# DECAWAVE.net
KiCad netlist of a schematic drawn in Altium Designer
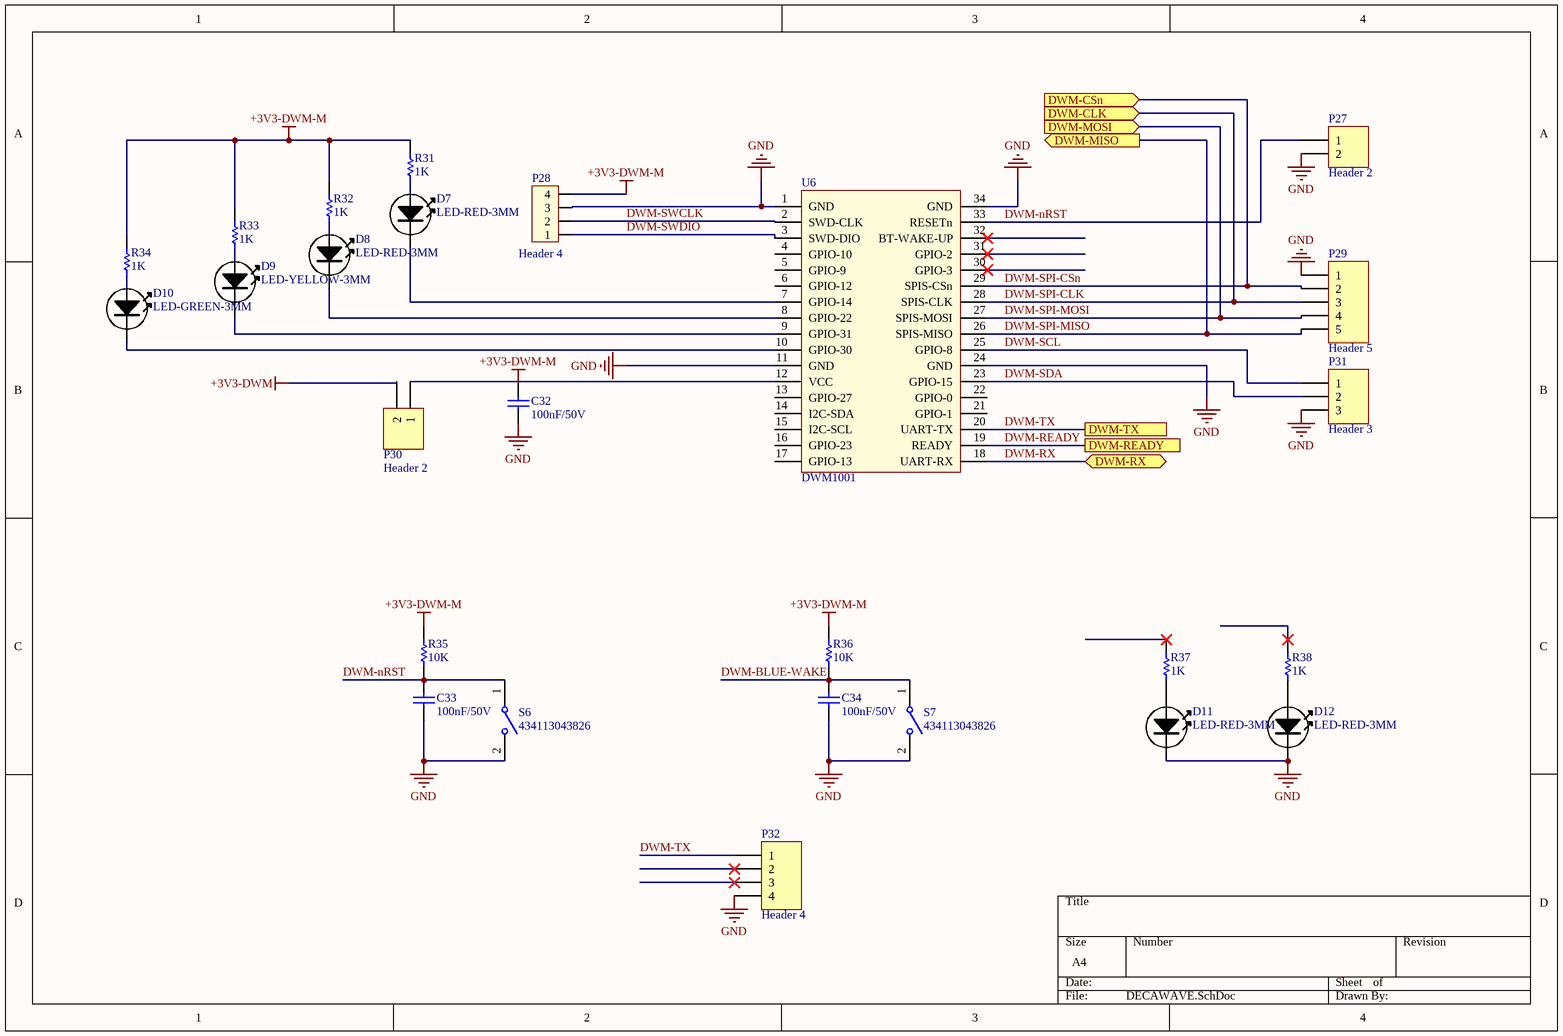
[diagram p0: DECAWAVE.SchDoc]

(export (version "E")
  (design (tool "Eeschema 10.0.6"))
  (components
    (comp (ref "C32")
      (value "100nF/50V")
      (footprint "CAP-SM-0805")
      (description "CAP CER 0.1UF 50V Y5V 0805")
      (fields
        (field (name "MANUFACTURER") "Samsung Electro-Mechanics")
        (field (name "MANUFACTURER PART NUMBER") "CL21F104ZBCNNNC")
      )
      (libsource (lib "Capacitor") (part "Cap-100nF-50V-0805"))
    )
    (comp (ref "C33")
      (value "100nF/50V")
      (footprint "CAP-SM-0805")
      (description "CAP CER 0.1UF 50V Y5V 0805")
      (fields
        (field (name "MANUFACTURER") "Samsung Electro-Mechanics")
        (field (name "MANUFACTURER PART NUMBER") "CL21F104ZBCNNNC")
      )
      (libsource (lib "Capacitor") (part "Cap-100nF-50V-0805"))
    )
    (comp (ref "C34")
      (value "100nF/50V")
      (footprint "CAP-SM-0805")
      (description "CAP CER 0.1UF 50V Y5V 0805")
      (fields
        (field (name "MANUFACTURER") "Samsung Electro-Mechanics")
        (field (name "MANUFACTURER PART NUMBER") "CL21F104ZBCNNNC")
      )
      (libsource (lib "Capacitor") (part "Cap-100nF-50V-0805"))
    )
    (comp (ref "D7")
      (value "LED-RED-3MM")
      (footprint "LED-3MM-RED")
      (libsource (lib "vh_altium_library") (part "LED-RED-3MM"))
    )
    (comp (ref "D8")
      (value "LED-RED-3MM")
      (footprint "LED-3MM-RED")
      (libsource (lib "vh_altium_library") (part "LED-RED-3MM"))
    )
    (comp (ref "D9")
      (value "LED-YELLOW-3MM")
      (footprint "LED-3MM-YELLOW")
      (libsource (lib "vh_altium_library") (part "LED-YELLOW-3MM"))
    )
    (comp (ref "D10")
      (value "LED-GREEN-3MM")
      (footprint "LED-3MM-GREEN")
      (libsource (lib "vh_altium_library") (part "LED-GREEN-3MM"))
    )
    (comp (ref "D11")
      (value "LED-RED-3MM")
      (footprint "LED-3MM-RED")
      (libsource (lib "vh_altium_library") (part "LED-RED-3MM"))
    )
    (comp (ref "D12")
      (value "LED-RED-3MM")
      (footprint "LED-3MM-RED")
      (libsource (lib "vh_altium_library") (part "LED-RED-3MM"))
    )
    (comp (ref "P27")
      (value "Header 2")
      (footprint "HDR1X2")
      (description "Header, 2-Pin")
      (fields (field (name "PUBLISHER") "Altium Limited"))
      (libsource (lib "") (part "Header 2_1"))
    )
    (comp (ref "P28")
      (value "Header 4")
      (footprint "HED4")
      (description "Header 4 (Green)")
      (libsource (lib "Library1") (part "Hed4"))
    )
    (comp (ref "P29")
      (value "Header 5")
      (footprint "HDR1X5")
      (description "Header, 5-Pin")
      (fields (field (name "PUBLISHER") "Altium Limited"))
      (libsource (lib "Library2") (part "Header 5"))
    )
    (comp (ref "P30")
      (value "Header 2")
      (footprint "HDR1X2")
      (description "Header, 2-Pin")
      (fields (field (name "PUBLISHER") "Altium Limited"))
      (libsource (lib "Library2") (part "Header 2"))
    )
    (comp (ref "P31")
      (value "Header 3")
      (footprint "HDR1X3")
      (description "Header, 3-Pin")
      (fields (field (name "PUBLISHER") "Altium Limited"))
      (libsource (lib "Library2") (part "Header 3"))
    )
    (comp (ref "P32")
      (value "Header 4")
      (footprint "HDR1X4")
      (description "Header, 4-Pin")
      (fields (field (name "PUBLISHER") "Altium Limited"))
      (libsource (lib "Library2") (part "Header 4"))
    )
    (comp (ref "R31")
      (value "1K")
      (footprint "Resistor:RES-SM-0805")
      (description "RES 1K OHM 1% 1/4W 0805")
      (fields
        (field (name "MANUFACTURER") "Stackpole Electronics Inc")
        (field (name "MANUFACTURER PART NUMBER") "RNCP0805FTD1K00")
      )
      (libsource (lib "Resistor") (part "Res-1K-0805"))
    )
    (comp (ref "R32")
      (value "1K")
      (footprint "Resistor:RES-SM-0805")
      (description "RES 1K OHM 1% 1/4W 0805")
      (fields
        (field (name "MANUFACTURER") "Stackpole Electronics Inc")
        (field (name "MANUFACTURER PART NUMBER") "RNCP0805FTD1K00")
      )
      (libsource (lib "Resistor") (part "Res-1K-0805"))
    )
    (comp (ref "R33")
      (value "1K")
      (footprint "Resistor:RES-SM-0805")
      (description "RES 1K OHM 1% 1/4W 0805")
      (fields
        (field (name "MANUFACTURER") "Stackpole Electronics Inc")
        (field (name "MANUFACTURER PART NUMBER") "RNCP0805FTD1K00")
      )
      (libsource (lib "Resistor") (part "Res-1K-0805"))
    )
    (comp (ref "R34")
      (value "1K")
      (footprint "Resistor:RES-SM-0805")
      (description "RES 1K OHM 1% 1/4W 0805")
      (fields
        (field (name "MANUFACTURER") "Stackpole Electronics Inc")
        (field (name "MANUFACTURER PART NUMBER") "RNCP0805FTD1K00")
      )
      (libsource (lib "Resistor") (part "Res-1K-0805"))
    )
    (comp (ref "R35")
      (value "10K")
      (footprint "Resistor:RES-SM-0805")
      (description "RES 10K OHM 1% 1/4W 0805")
      (fields
        (field (name "MANUFACTURER") "Stackpole Electronics Inc")
        (field (name "MANUFACTURER PART NUMBER") "RNCP0805FTD10K0")
      )
      (libsource (lib "Resistor") (part "Res-10k-0805"))
    )
    (comp (ref "R36")
      (value "10K")
      (footprint "Resistor:RES-SM-0805")
      (description "RES 10K OHM 1% 1/4W 0805")
      (fields
        (field (name "MANUFACTURER") "Stackpole Electronics Inc")
        (field (name "MANUFACTURER PART NUMBER") "RNCP0805FTD10K0")
      )
      (libsource (lib "Resistor") (part "Res-10k-0805"))
    )
    (comp (ref "R37")
      (value "1K")
      (footprint "Resistor:RES-SM-0805")
      (description "RES 1K OHM 1% 1/4W 0805")
      (fields
        (field (name "MANUFACTURER") "Stackpole Electronics Inc")
        (field (name "MANUFACTURER PART NUMBER") "RNCP0805FTD1K00")
      )
      (libsource (lib "Resistor") (part "Res-1K-0805"))
    )
    (comp (ref "R38")
      (value "1K")
      (footprint "Resistor:RES-SM-0805")
      (description "RES 1K OHM 1% 1/4W 0805")
      (fields
        (field (name "MANUFACTURER") "Stackpole Electronics Inc")
        (field (name "MANUFACTURER PART NUMBER") "RNCP0805FTD1K00")
      )
      (libsource (lib "Resistor") (part "Res-1K-0805"))
    )
    (comp (ref "S6")
      (value "434113043826")
      (footprint "434113043826")
      (description "WS-TASV J-Bend SMT Tact Switch 6x3.5mm, height 4.3mm, 260gf")
      (fields (field (name "PUBLISHER") "Wurth Elektronik"))
      (libsource (lib "434113043826_Altium_WS-TASV_rev20a") (part "434113043826"))
    )
    (comp (ref "S7")
      (value "434113043826")
      (footprint "434113043826")
      (description "WS-TASV J-Bend SMT Tact Switch 6x3.5mm, height 4.3mm, 260gf")
      (fields (field (name "PUBLISHER") "Wurth Elektronik"))
      (libsource (lib "434113043826_Altium_WS-TASV_rev20a") (part "434113043826"))
    )
    (comp (ref "U6") (value "DWM1001") (libsource (lib "MyLibrary1") (part "DWM1001")))
  )
  (nets
    (net (code "1") (name "+3V3-DWM") (class "Default")
      (node (ref "P30") (pin "2") (pinfunction "2_2") (pintype "passive"))
    )
    (net (code "2") (name "+3V3-DWM-M") (class "Default")
      (node (ref "C32") (pin "2") (pinfunction "2_2") (pintype "passive"))
      (node (ref "P28") (pin "4") (pinfunction "4_4") (pintype "passive"))
      (node (ref "R31") (pin "2") (pinfunction "2_2") (pintype "passive"))
      (node (ref "R32") (pin "2") (pinfunction "2_2") (pintype "passive"))
      (node (ref "R33") (pin "2") (pinfunction "2_2") (pintype "passive"))
      (node (ref "R34") (pin "2") (pinfunction "2_2") (pintype "passive"))
      (node (ref "R35") (pin "2") (pinfunction "2_2") (pintype "passive"))
      (node (ref "R36") (pin "2") (pinfunction "2_2") (pintype "passive"))
    )
    (net (code "3") (name "/DWM-BLUE-WAKE") (class "Default")
      (node (ref "C34") (pin "2") (pinfunction "2_2") (pintype "passive"))
      (node (ref "R36") (pin "1") (pinfunction "1_1") (pintype "passive"))
      (node (ref "S7") (pin "1") (pinfunction "1_1") (pintype "passive"))
    )
    (net (code "4") (name "/DWM-READY") (class "Default")
      (node (ref "U6") (pin "19") (pinfunction "READY_19") (pintype "passive"))
    )
    (net (code "5") (name "/DWM-RX") (class "Default")
      (node (ref "U6") (pin "18") (pinfunction "UART-RX_18") (pintype "passive"))
    )
    (net (code "6") (name "/DWM-SCL") (class "Default")
      (node (ref "P31") (pin "1") (pinfunction "1_1") (pintype "passive"))
      (node (ref "U6") (pin "25") (pinfunction "GPIO-8_25") (pintype "passive"))
    )
    (net (code "7") (name "/DWM-SDA") (class "Default")
      (node (ref "P31") (pin "2") (pinfunction "2_2") (pintype "passive"))
      (node (ref "U6") (pin "23") (pinfunction "GPIO-15_23") (pintype "passive"))
    )
    (net (code "8") (name "/DWM-SPI-CLK") (class "Default")
      (node (ref "P29") (pin "3") (pinfunction "3_3") (pintype "passive"))
      (node (ref "U6") (pin "28") (pinfunction "SPIS-CLK_28") (pintype "passive"))
    )
    (net (code "9") (name "/DWM-SPI-CSn") (class "Default")
      (node (ref "P29") (pin "2") (pinfunction "2_2") (pintype "passive"))
      (node (ref "U6") (pin "29") (pinfunction "SPIS-CSn_29") (pintype "passive"))
    )
    (net (code "10") (name "/DWM-SPI-MISO") (class "Default")
      (node (ref "P29") (pin "5") (pinfunction "5_5") (pintype "passive"))
      (node (ref "U6") (pin "26") (pinfunction "SPIS-MISO_26") (pintype "passive"))
    )
    (net (code "11") (name "/DWM-SPI-MOSI") (class "Default")
      (node (ref "P29") (pin "4") (pinfunction "4_4") (pintype "passive"))
      (node (ref "U6") (pin "27") (pinfunction "SPIS-MOSI_27") (pintype "passive"))
    )
    (net (code "12") (name "/DWM-SWCLK") (class "Default")
      (node (ref "P28") (pin "2") (pinfunction "2_2") (pintype "passive"))
      (node (ref "U6") (pin "2") (pinfunction "SWD-CLK_2") (pintype "passive"))
    )
    (net (code "13") (name "/DWM-SWDIO") (class "Default")
      (node (ref "P28") (pin "1") (pinfunction "1_1") (pintype "passive"))
      (node (ref "U6") (pin "3") (pinfunction "SWD-DIO_3") (pintype "passive"))
    )
    (net (code "14") (name "/DWM-TX") (class "Default")
      (node (ref "P32") (pin "1") (pinfunction "1_1") (pintype "passive"))
      (node (ref "U6") (pin "20") (pinfunction "UART-TX_20") (pintype "passive"))
    )
    (net (code "15") (name "/DWM-nRST") (class "Default")
      (node (ref "C33") (pin "2") (pinfunction "2_2") (pintype "passive"))
      (node (ref "P27") (pin "1") (pinfunction "1_1") (pintype "passive"))
      (node (ref "R35") (pin "1") (pinfunction "1_1") (pintype "passive"))
      (node (ref "S6") (pin "1") (pinfunction "1_1") (pintype "passive"))
      (node (ref "U6") (pin "33") (pinfunction "RESETn_33") (pintype "passive"))
    )
    (net (code "16") (name "GND") (class "Default")
      (node (ref "C32") (pin "1") (pinfunction "1_1") (pintype "passive"))
      (node (ref "C33") (pin "1") (pinfunction "1_1") (pintype "passive"))
      (node (ref "C34") (pin "1") (pinfunction "1_1") (pintype "passive"))
      (node (ref "D11") (pin "K") (pintype "passive"))
      (node (ref "D12") (pin "K") (pintype "passive"))
      (node (ref "P27") (pin "2") (pinfunction "2_2") (pintype "passive"))
      (node (ref "P28") (pin "3") (pinfunction "3_3") (pintype "passive"))
      (node (ref "P29") (pin "1") (pinfunction "1_1") (pintype "passive"))
      (node (ref "P31") (pin "3") (pinfunction "3_3") (pintype "passive"))
      (node (ref "P32") (pin "4") (pinfunction "4_4") (pintype "passive"))
      (node (ref "S6") (pin "2") (pinfunction "2_2") (pintype "passive"))
      (node (ref "S7") (pin "2") (pinfunction "2_2") (pintype "passive"))
      (node (ref "U6") (pin "1") (pinfunction "GND_1") (pintype "passive"))
      (node (ref "U6") (pin "11") (pinfunction "GND_11") (pintype "passive"))
      (node (ref "U6") (pin "24") (pinfunction "GND_24") (pintype "passive"))
      (node (ref "U6") (pin "34") (pinfunction "GND_34") (pintype "passive"))
    )
    (net (code "17") (name "Net-(D7-PadA)") (class "Default")
      (node (ref "D7") (pin "A") (pintype "passive"))
      (node (ref "R31") (pin "1") (pinfunction "1_1") (pintype "passive"))
    )
    (net (code "18") (name "Net-(D8-PadA)") (class "Default")
      (node (ref "D8") (pin "A") (pintype "passive"))
      (node (ref "R32") (pin "1") (pinfunction "1_1") (pintype "passive"))
    )
    (net (code "19") (name "Net-(D9-PadA)") (class "Default")
      (node (ref "D9") (pin "A") (pintype "passive"))
      (node (ref "R33") (pin "1") (pinfunction "1_1") (pintype "passive"))
    )
    (net (code "20") (name "Net-(D10-PadA)") (class "Default")
      (node (ref "D10") (pin "A") (pintype "passive"))
      (node (ref "R34") (pin "1") (pinfunction "1_1") (pintype "passive"))
    )
    (net (code "21") (name "Net-(D11-PadA)") (class "Default")
      (node (ref "D11") (pin "A") (pintype "passive"))
      (node (ref "R37") (pin "1") (pinfunction "1_1") (pintype "passive"))
    )
    (net (code "22") (name "Net-(D12-PadA)") (class "Default")
      (node (ref "D12") (pin "A") (pintype "passive"))
      (node (ref "R38") (pin "1") (pinfunction "1_1") (pintype "passive"))
    )
    (net (code "23") (name "Net-(U6-GPIO-14)") (class "Default")
      (node (ref "D7") (pin "K") (pintype "passive"))
      (node (ref "U6") (pin "7") (pinfunction "GPIO-14_7") (pintype "passive"))
    )
    (net (code "24") (name "Net-(U6-GPIO-22)") (class "Default")
      (node (ref "D8") (pin "K") (pintype "passive"))
      (node (ref "U6") (pin "8") (pinfunction "GPIO-22_8") (pintype "passive"))
    )
    (net (code "25") (name "Net-(U6-GPIO-30)") (class "Default")
      (node (ref "D10") (pin "K") (pintype "passive"))
      (node (ref "U6") (pin "10") (pinfunction "GPIO-30_10") (pintype "passive"))
    )
    (net (code "26") (name "Net-(U6-GPIO-31)") (class "Default")
      (node (ref "D9") (pin "K") (pintype "passive"))
      (node (ref "U6") (pin "9") (pinfunction "GPIO-31_9") (pintype "passive"))
    )
    (net (code "27") (name "Net-(U6-VCC)") (class "Default")
      (node (ref "P30") (pin "1") (pinfunction "1_1") (pintype "passive"))
      (node (ref "U6") (pin "12") (pinfunction "VCC_12") (pintype "passive"))
    )
    (net (code "28") (name "unconnected-(P32-Pad2)") (class "Default")
      (node (ref "P32") (pin "2") (pinfunction "2_2") (pintype "passive+no_connect"))
    )
    (net (code "29") (name "unconnected-(P32-Pad3)") (class "Default")
      (node (ref "P32") (pin "3") (pinfunction "3_3") (pintype "passive+no_connect"))
    )
    (net (code "30") (name "unconnected-(R37-Pad2)") (class "Default")
      (node (ref "R37") (pin "2") (pinfunction "2_2") (pintype "passive+no_connect"))
    )
    (net (code "31") (name "unconnected-(R38-Pad2)") (class "Default")
      (node (ref "R38") (pin "2") (pinfunction "2_2") (pintype "passive+no_connect"))
    )
    (net (code "32") (name "unconnected-(U6-BT-WAKE-UP-Pad32)") (class "Default")
      (node (ref "U6") (pin "32") (pinfunction "BT-WAKE-UP_32") (pintype "passive+no_connect"))
    )
    (net (code "33") (name "unconnected-(U6-GPIO-0-Pad22)") (class "Default")
      (node (ref "U6") (pin "22") (pinfunction "GPIO-0_22") (pintype "passive"))
    )
    (net (code "34") (name "unconnected-(U6-GPIO-1-Pad21)") (class "Default")
      (node (ref "U6") (pin "21") (pinfunction "GPIO-1_21") (pintype "passive"))
    )
    (net (code "35") (name "unconnected-(U6-GPIO-2-Pad31)") (class "Default")
      (node (ref "U6") (pin "31") (pinfunction "GPIO-2_31") (pintype "passive+no_connect"))
    )
    (net (code "36") (name "unconnected-(U6-GPIO-3-Pad30)") (class "Default")
      (node (ref "U6") (pin "30") (pinfunction "GPIO-3_30") (pintype "passive+no_connect"))
    )
    (net (code "37") (name "unconnected-(U6-GPIO-9-Pad5)") (class "Default")
      (node (ref "U6") (pin "5") (pinfunction "GPIO-9_5") (pintype "passive"))
    )
    (net (code "38") (name "unconnected-(U6-GPIO-10-Pad4)") (class "Default")
      (node (ref "U6") (pin "4") (pinfunction "GPIO-10_4") (pintype "passive"))
    )
    (net (code "39") (name "unconnected-(U6-GPIO-12-Pad6)") (class "Default")
      (node (ref "U6") (pin "6") (pinfunction "GPIO-12_6") (pintype "passive"))
    )
    (net (code "40") (name "unconnected-(U6-GPIO-13-Pad17)") (class "Default")
      (node (ref "U6") (pin "17") (pinfunction "GPIO-13_17") (pintype "passive"))
    )
    (net (code "41") (name "unconnected-(U6-GPIO-23-Pad16)") (class "Default")
      (node (ref "U6") (pin "16") (pinfunction "GPIO-23_16") (pintype "passive"))
    )
    (net (code "42") (name "unconnected-(U6-GPIO-27-Pad13)") (class "Default")
      (node (ref "U6") (pin "13") (pinfunction "GPIO-27_13") (pintype "passive"))
    )
    (net (code "43") (name "unconnected-(U6-I2C-SCL-Pad15)") (class "Default")
      (node (ref "U6") (pin "15") (pinfunction "I2C-SCL_15") (pintype "passive"))
    )
    (net (code "44") (name "unconnected-(U6-I2C-SDA-Pad14)") (class "Default")
      (node (ref "U6") (pin "14") (pinfunction "I2C-SDA_14") (pintype "passive"))
    )
  )
)
